# CAN_interface.net
KiCad netlist of a schematic drawn in Altium Designer
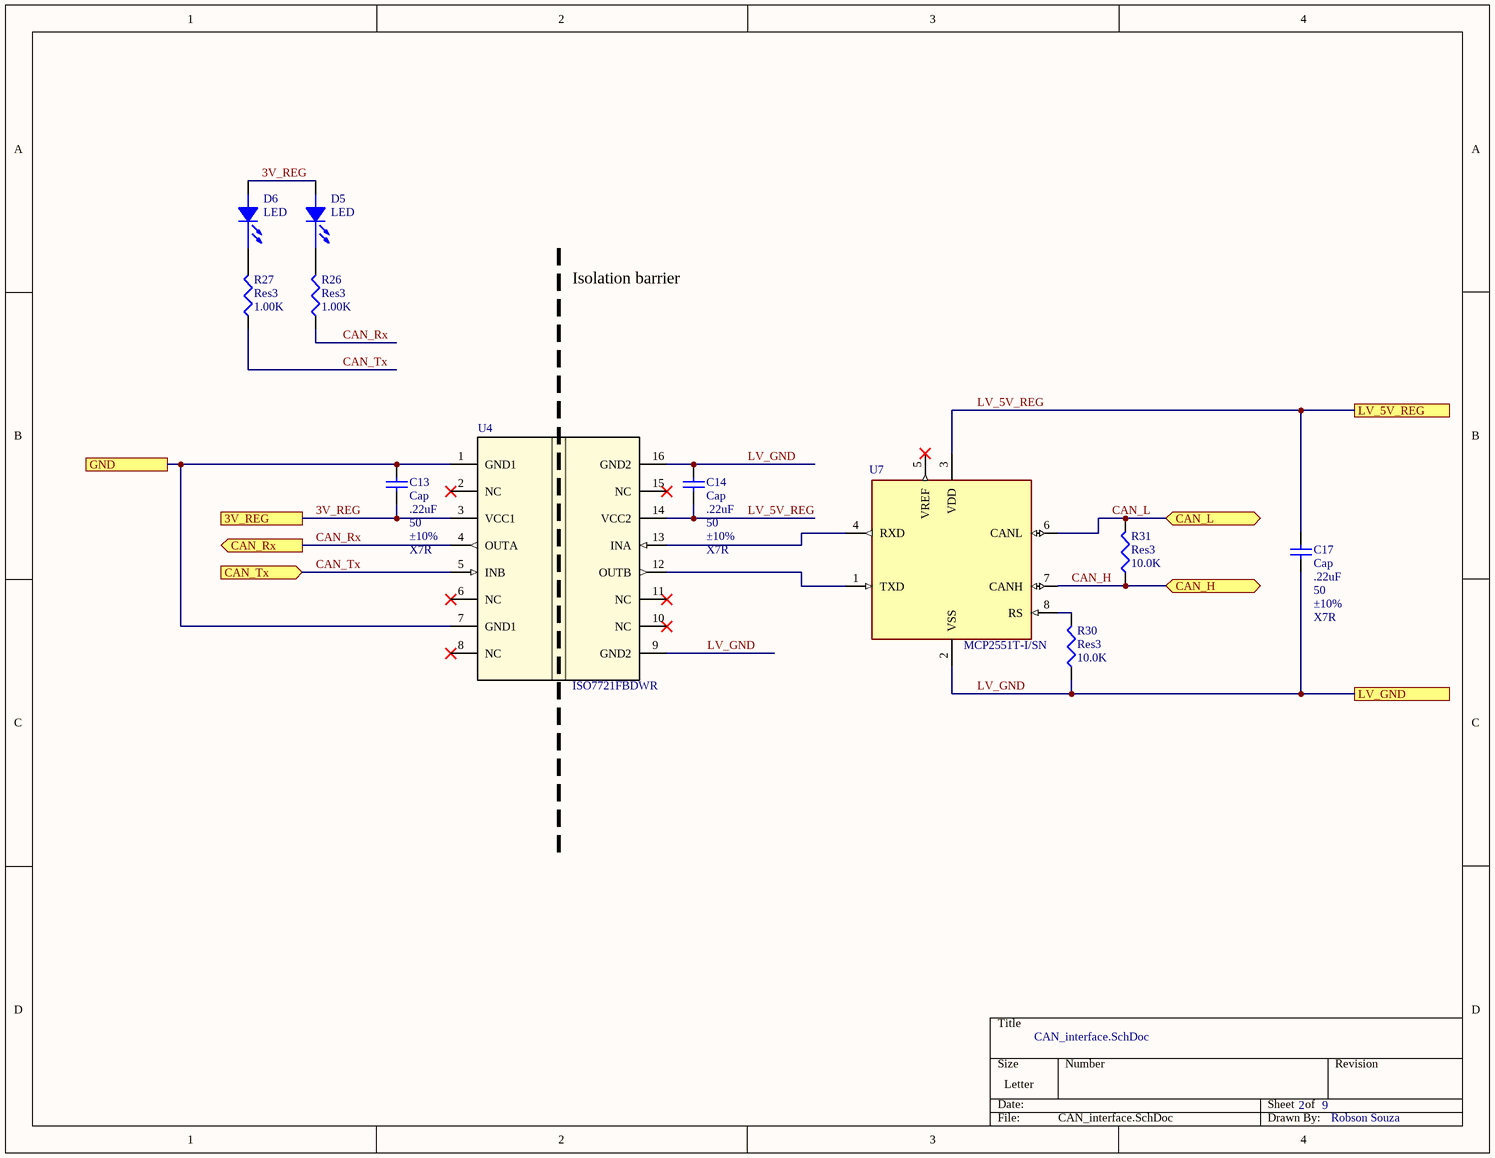
[diagram p0: CAN_interface.SchDoc]

(export (version "E")
  (design (tool "Eeschema 10.0.6"))
  (components
    (comp (ref "C13")
      (value "Cap")
      (footprint "CAPC2012X09M")
      (description "CAP CER .22uF 50v X7R 0805")
      (fields
        (field (name "ALTIUM_VALUE") ".22uF")
        (field (name "WV") "50")
        (field (name "TOLERANCE") "±10%")
        (field (name "TYPE") "X7R")
        (field (name "MPN") "C0805C224K5RACTU")
      )
      (libsource (lib "esd_library") (part "CAP-X7R-.22uF-50V-±10%"))
    )
    (comp (ref "C14")
      (value "Cap")
      (footprint "CAPC2012X09M")
      (description "CAP CER .22uF 50v X7R 0805")
      (fields
        (field (name "ALTIUM_VALUE") ".22uF")
        (field (name "WV") "50")
        (field (name "TOLERANCE") "±10%")
        (field (name "TYPE") "X7R")
        (field (name "MPN") "C0805C224K5RACTU")
      )
      (libsource (lib "esd_library") (part "CAP-X7R-.22uF-50V-±10%"))
    )
    (comp (ref "C17")
      (value "Cap")
      (footprint "CAPC2012X09M")
      (description "CAP CER .22uF 50v X7R 0805")
      (fields
        (field (name "ALTIUM_VALUE") ".22uF")
        (field (name "WV") "50")
        (field (name "TOLERANCE") "±10%")
        (field (name "TYPE") "X7R")
        (field (name "MPN") "C0805C224K5RACTU")
      )
      (libsource (lib "esd_library") (part "CAP-X7R-.22uF-50V-±10%"))
    )
    (comp (ref "D5") (value "LED") (footprint "0603") (libsource (lib "esd_library") (part "LED")))
    (comp (ref "D6") (value "LED") (footprint "0603") (libsource (lib "esd_library") (part "LED")))
    (comp (ref "R26")
      (value "Res3")
      (footprint "RESC2112X05M")
      (description "RES SMD 1.00K OHM 1% 1/8W 0805")
      (fields (field (name "ALTIUM_VALUE") "1.00K") (field (name "MPN") "CRCW08051K00FKEA"))
      (libsource (lib "esd_library") (part "Resistor_1.00K"))
    )
    (comp (ref "R27")
      (value "Res3")
      (footprint "RESC2112X05M")
      (description "RES SMD 1.00K OHM 1% 1/8W 0805")
      (fields (field (name "ALTIUM_VALUE") "1.00K") (field (name "MPN") "CRCW08051K00FKEA"))
      (libsource (lib "esd_library") (part "Resistor_1.00K"))
    )
    (comp (ref "R30")
      (value "Res3")
      (footprint "RESC2112X05M")
      (description "RES SMD 10.0K OHM 1% 1/8W 0805")
      (fields (field (name "ALTIUM_VALUE") "10.0K") (field (name "MPN") "CRCW080510K0FKEA"))
      (libsource (lib "esd_library") (part "Resistor_10.0K"))
    )
    (comp (ref "R31")
      (value "Res3")
      (footprint "RESC2112X05M")
      (description "RES SMD 10.0K OHM 1% 1/8W 0805")
      (fields (field (name "ALTIUM_VALUE") "10.0K") (field (name "MPN") "CRCW080510K0FKEA"))
      (libsource (lib "esd_library") (part "Resistor_10.0K"))
    )
    (comp (ref "U4")
      (value "ISO7721FBDWR")
      (footprint "DW0016B_N")
      (description "Digital Isolador")
      (fields (field (name "COPYRIGHT") "Copyright (C) 2022 Ultra Librarian. All rights reserved."))
      (libsource (lib "ISO7721FBDWR") (part "ISO7721FBDWR"))
    )
    (comp (ref "U7")
      (value "MCP2551T-I/SN")
      (footprint "SOIC127P600X175-8N")
      (description "1/1 Transceiver Half CANbus 8-SOIC")
      (fields (field (name "MF") "Microchip"))
      (libsource (lib "MCP2551T-I_SN") (part "MCP2551T-I/SN"))
    )
  )
  (nets
    (net (code "1") (name "/3V_REG") (class "Default")
      (node (ref "C13") (pin "1") (pinfunction "1_1") (pintype "passive"))
      (node (ref "D5") (pin "1") (pinfunction "A_1") (pintype "passive"))
      (node (ref "D6") (pin "1") (pinfunction "A_1") (pintype "passive"))
      (node (ref "U4") (pin "3") (pinfunction "VCC1_3") (pintype "power_in"))
    )
    (net (code "2") (name "/CAN_H") (class "Default")
      (node (ref "R31") (pin "1") (pinfunction "1_1") (pintype "passive"))
      (node (ref "U7") (pin "7") (pinfunction "CANH_7") (pintype "bidirectional"))
    )
    (net (code "3") (name "/CAN_L") (class "Default")
      (node (ref "R31") (pin "2") (pinfunction "2_2") (pintype "passive"))
      (node (ref "U7") (pin "6") (pinfunction "CANL_6") (pintype "bidirectional"))
    )
    (net (code "4") (name "/CAN_Rx") (class "Default")
      (node (ref "R26") (pin "1") (pinfunction "1_1") (pintype "passive"))
      (node (ref "U4") (pin "4") (pinfunction "OUTA_4") (pintype "output"))
    )
    (net (code "5") (name "/CAN_Tx") (class "Default")
      (node (ref "R27") (pin "1") (pinfunction "1_1") (pintype "passive"))
      (node (ref "U4") (pin "5") (pinfunction "INB_5") (pintype "input"))
    )
    (net (code "6") (name "/GND") (class "Default")
      (node (ref "C13") (pin "2") (pinfunction "2_2") (pintype "passive"))
      (node (ref "U4") (pin "1") (pinfunction "GND1_1") (pintype "power_in"))
      (node (ref "U4") (pin "7") (pinfunction "GND1_7") (pintype "power_in"))
    )
    (net (code "7") (name "/LV_5V_REG") (class "Default")
      (node (ref "C14") (pin "2") (pinfunction "2_2") (pintype "passive"))
      (node (ref "C17") (pin "1") (pinfunction "1_1") (pintype "passive"))
      (node (ref "U4") (pin "14") (pinfunction "VCC2_14") (pintype "power_in"))
      (node (ref "U7") (pin "3") (pinfunction "VDD_3") (pintype "power_in"))
    )
    (net (code "8") (name "/LV_GND") (class "Default")
      (node (ref "C14") (pin "1") (pinfunction "1_1") (pintype "passive"))
      (node (ref "C17") (pin "2") (pinfunction "2_2") (pintype "passive"))
      (node (ref "R30") (pin "1") (pinfunction "1_1") (pintype "passive"))
      (node (ref "U4") (pin "16") (pinfunction "GND2_16") (pintype "power_in"))
      (node (ref "U4") (pin "9") (pinfunction "GND2_9") (pintype "power_in"))
      (node (ref "U7") (pin "2") (pinfunction "VSS_2") (pintype "passive"))
    )
    (net (code "9") (name "Net-(D5-C)") (class "Default")
      (node (ref "D5") (pin "2") (pinfunction "C_2") (pintype "passive"))
      (node (ref "R26") (pin "2") (pinfunction "2_2") (pintype "passive"))
    )
    (net (code "10") (name "Net-(D6-C)") (class "Default")
      (node (ref "D6") (pin "2") (pinfunction "C_2") (pintype "passive"))
      (node (ref "R27") (pin "2") (pinfunction "2_2") (pintype "passive"))
    )
    (net (code "11") (name "Net-(U4-INA)") (class "Default")
      (node (ref "U4") (pin "13") (pinfunction "INA_13") (pintype "input"))
      (node (ref "U7") (pin "4") (pinfunction "RXD_4") (pintype "output"))
    )
    (net (code "12") (name "Net-(U4-OUTB)") (class "Default")
      (node (ref "U4") (pin "12") (pinfunction "OUTB_12") (pintype "output"))
      (node (ref "U7") (pin "1") (pinfunction "TXD_1") (pintype "input"))
    )
    (net (code "13") (name "Net-(U7-RS)") (class "Default")
      (node (ref "R30") (pin "2") (pinfunction "2_2") (pintype "passive"))
      (node (ref "U7") (pin "8") (pinfunction "RS_8") (pintype "input"))
    )
    (net (code "14") (name "unconnected-(U4-NC-Pad2)") (class "Default")
      (node (ref "U4") (pin "2") (pinfunction "NC_2") (pintype "passive+no_connect"))
    )
    (net (code "15") (name "unconnected-(U4-NC-Pad6)") (class "Default")
      (node (ref "U4") (pin "6") (pinfunction "NC_6") (pintype "passive+no_connect"))
    )
    (net (code "16") (name "unconnected-(U4-NC-Pad8)") (class "Default")
      (node (ref "U4") (pin "8") (pinfunction "NC_8") (pintype "passive+no_connect"))
    )
    (net (code "17") (name "unconnected-(U4-NC-Pad10)") (class "Default")
      (node (ref "U4") (pin "10") (pinfunction "NC_10") (pintype "passive+no_connect"))
    )
    (net (code "18") (name "unconnected-(U4-NC-Pad11)") (class "Default")
      (node (ref "U4") (pin "11") (pinfunction "NC_11") (pintype "passive+no_connect"))
    )
    (net (code "19") (name "unconnected-(U4-NC-Pad15)") (class "Default")
      (node (ref "U4") (pin "15") (pinfunction "NC_15") (pintype "passive+no_connect"))
    )
    (net (code "20") (name "unconnected-(U7-VREF-Pad5)") (class "Default")
      (node (ref "U7") (pin "5") (pinfunction "VREF_5") (pintype "output+no_connect"))
    )
  )
)
